# Schematics.net
KiCad netlist of a schematic drawn in Altium Designer
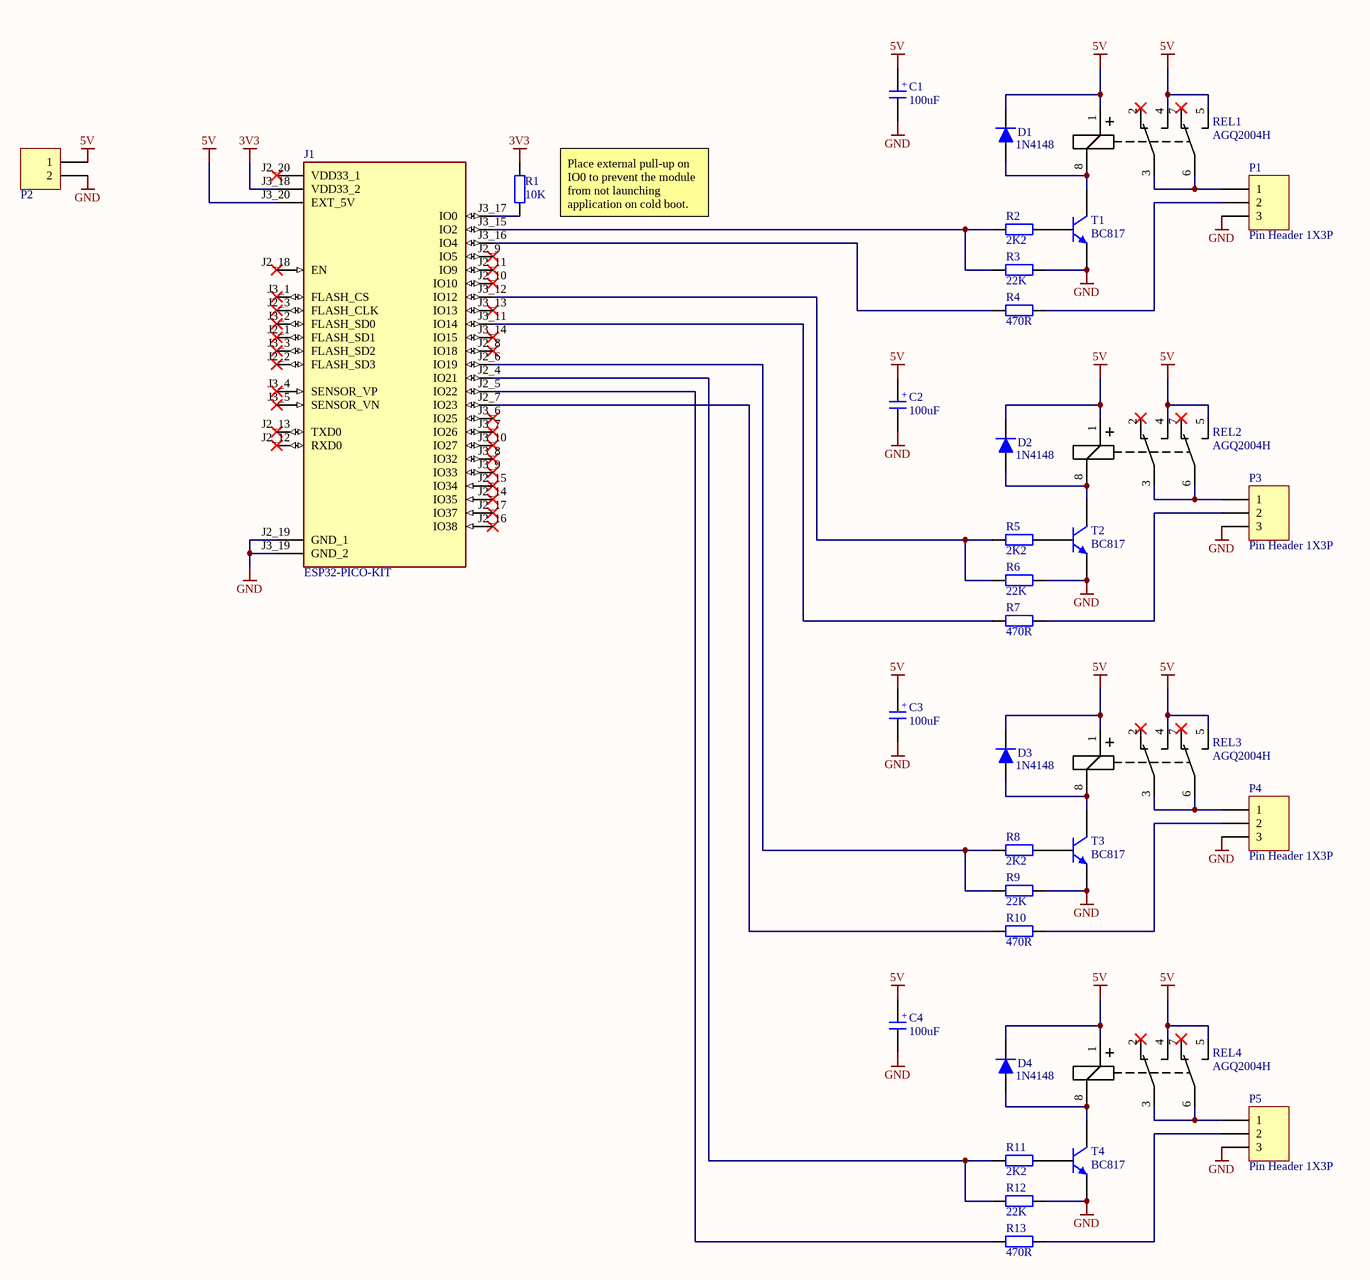
[diagram p0: Schematics.SchDoc]

(export (version "E")
  (design (tool "Eeschema 10.0.6"))
  (components
    (comp (ref "C1")
      (value "100uF")
      (footprint "EM-Alu-Elco_6,3X8_SMD")
      (description "Capacitor Elco")
      (libsource (lib "SchematicLibrary") (part "Capacitor Elco"))
    )
    (comp (ref "C2")
      (value "100uF")
      (footprint "EM-Alu-Elco_6,3X8_SMD")
      (description "Capacitor Elco")
      (libsource (lib "SchematicLibrary") (part "Capacitor Elco"))
    )
    (comp (ref "C3")
      (value "100uF")
      (footprint "EM-Alu-Elco_6,3X8_SMD")
      (description "Capacitor Elco")
      (libsource (lib "SchematicLibrary") (part "Capacitor Elco"))
    )
    (comp (ref "C4")
      (value "100uF")
      (footprint "EM-Alu-Elco_6,3X8_SMD")
      (description "Capacitor Elco")
      (libsource (lib "SchematicLibrary") (part "Capacitor Elco"))
    )
    (comp (ref "D1")
      (value "1N4148")
      (footprint "EM-SOD80C T1,5_SMD")
      (description "Diode")
      (libsource (lib "SchematicLibrary") (part "Diode"))
    )
    (comp (ref "D2")
      (value "1N4148")
      (footprint "EM-SOD80C T1,5_SMD")
      (description "Diode")
      (libsource (lib "SchematicLibrary") (part "Diode"))
    )
    (comp (ref "D3")
      (value "1N4148")
      (footprint "EM-SOD80C T1,5_SMD")
      (description "Diode")
      (libsource (lib "SchematicLibrary") (part "Diode"))
    )
    (comp (ref "D4")
      (value "1N4148")
      (footprint "EM-SOD80C T1,5_SMD")
      (description "Diode")
      (libsource (lib "SchematicLibrary") (part "Diode"))
    )
    (comp (ref "J1")
      (value "ESP32-PICO-KIT")
      (footprint "XCVR_ESP32-PICO-KIT")
      (fields (field (name "MF") "Espressif Systems"))
      (libsource (lib "SchematicLibrary") (part "ESP32-PICO-KIT"))
    )
    (comp (ref "P1")
      (value "Pin Header 1X3P")
      (footprint "JST XH B3B-XH-A")
      (description "Header 3-Pin")
      (fields (field (name "MANUFACTURER PART NO.") "61300311121"))
      (libsource (lib "SchematicLibrary") (part "Header 3"))
    )
    (comp (ref "P2")
      (value "Pin Header 1X2P")
      (footprint "JST XH B2B-XH-A")
      (description "Header 2-Pin")
      (fields (field (name "MANUFACTURER PART NO.") "61300211121"))
      (libsource (lib "SchematicLibrary") (part "Header 2"))
    )
    (comp (ref "P3")
      (value "Pin Header 1X3P")
      (footprint "JST XH B3B-XH-A")
      (description "Header 3-Pin")
      (fields (field (name "MANUFACTURER PART NO.") "61300311121"))
      (libsource (lib "SchematicLibrary") (part "Header 3"))
    )
    (comp (ref "P4")
      (value "Pin Header 1X3P")
      (footprint "JST XH B3B-XH-A")
      (description "Header 3-Pin")
      (fields (field (name "MANUFACTURER PART NO.") "61300311121"))
      (libsource (lib "SchematicLibrary") (part "Header 3"))
    )
    (comp (ref "P5")
      (value "Pin Header 1X3P")
      (footprint "JST XH B3B-XH-A")
      (description "Header 3-Pin")
      (fields (field (name "MANUFACTURER PART NO.") "61300311121"))
      (libsource (lib "SchematicLibrary") (part "Header 3"))
    )
    (comp (ref "R1")
      (value "10K")
      (footprint "EM-0603-R T0,45_SMD")
      (description "Resistor")
      (libsource (lib "") (part "Resistor_1"))
    )
    (comp (ref "R2")
      (value "2K2")
      (footprint "EM-0603-R T0,45_SMD")
      (description "Resistor")
      (libsource (lib "SchematicLibrary") (part "Resistor"))
    )
    (comp (ref "R3")
      (value "22K")
      (footprint "EM-0603-R T0,45_SMD")
      (description "Resistor")
      (libsource (lib "SchematicLibrary") (part "Resistor"))
    )
    (comp (ref "R4")
      (value "470R")
      (footprint "EM-0603-R T0,45_SMD")
      (description "Resistor")
      (libsource (lib "SchematicLibrary") (part "Resistor"))
    )
    (comp (ref "R5")
      (value "2K2")
      (footprint "EM-0603-R T0,45_SMD")
      (description "Resistor")
      (libsource (lib "SchematicLibrary") (part "Resistor"))
    )
    (comp (ref "R6")
      (value "22K")
      (footprint "EM-0603-R T0,45_SMD")
      (description "Resistor")
      (libsource (lib "SchematicLibrary") (part "Resistor"))
    )
    (comp (ref "R7")
      (value "470R")
      (footprint "EM-0603-R T0,45_SMD")
      (description "Resistor")
      (libsource (lib "SchematicLibrary") (part "Resistor"))
    )
    (comp (ref "R8")
      (value "2K2")
      (footprint "EM-0603-R T0,45_SMD")
      (description "Resistor")
      (libsource (lib "SchematicLibrary") (part "Resistor"))
    )
    (comp (ref "R9")
      (value "22K")
      (footprint "EM-0603-R T0,45_SMD")
      (description "Resistor")
      (libsource (lib "SchematicLibrary") (part "Resistor"))
    )
    (comp (ref "R10")
      (value "470R")
      (footprint "EM-0603-R T0,45_SMD")
      (description "Resistor")
      (libsource (lib "SchematicLibrary") (part "Resistor"))
    )
    (comp (ref "R11")
      (value "2K2")
      (footprint "EM-0603-R T0,45_SMD")
      (description "Resistor")
      (libsource (lib "SchematicLibrary") (part "Resistor"))
    )
    (comp (ref "R12")
      (value "22K")
      (footprint "EM-0603-R T0,45_SMD")
      (description "Resistor")
      (libsource (lib "SchematicLibrary") (part "Resistor"))
    )
    (comp (ref "R13")
      (value "470R")
      (footprint "EM-0603-R T0,45_SMD")
      (description "Resistor")
      (libsource (lib "SchematicLibrary") (part "Resistor"))
    )
    (comp (ref "REL1")
      (value "AGQ2004H")
      (footprint "THC Relay AGQ")
      (description "AGQ2004H -  Signal Relay, 4.5 VDC, DPDT, 2 A, Through Hole, Non Latching, AGQ Series")
      (fields (field (name "MANUFACTURER PART NO.") "TX2-4.5V") (field (name "TYPE") "AGQ2004H"))
      (libsource (lib "SchematicLibrary") (part "Relay AGQ2004H"))
    )
    (comp (ref "REL2")
      (value "AGQ2004H")
      (footprint "THC Relay AGQ")
      (description "AGQ2004H -  Signal Relay, 4.5 VDC, DPDT, 2 A, Through Hole, Non Latching, AGQ Series")
      (fields (field (name "MANUFACTURER PART NO.") "TX2-4.5V") (field (name "TYPE") "AGQ2004H"))
      (libsource (lib "SchematicLibrary") (part "Relay AGQ2004H"))
    )
    (comp (ref "REL3")
      (value "AGQ2004H")
      (footprint "THC Relay AGQ")
      (description "AGQ2004H -  Signal Relay, 4.5 VDC, DPDT, 2 A, Through Hole, Non Latching, AGQ Series")
      (fields (field (name "MANUFACTURER PART NO.") "TX2-4.5V") (field (name "TYPE") "AGQ2004H"))
      (libsource (lib "SchematicLibrary") (part "Relay AGQ2004H"))
    )
    (comp (ref "REL4")
      (value "AGQ2004H")
      (footprint "THC Relay AGQ")
      (description "AGQ2004H -  Signal Relay, 4.5 VDC, DPDT, 2 A, Through Hole, Non Latching, AGQ Series")
      (fields (field (name "MANUFACTURER PART NO.") "TX2-4.5V") (field (name "TYPE") "AGQ2004H"))
      (libsource (lib "SchematicLibrary") (part "Relay AGQ2004H"))
    )
    (comp (ref "T1")
      (value "BC817")
      (footprint "EM-SOT323_SMD")
      (description "BC817 -  Bipolar (BJT) Single Transistor, NPN, 45 V, 170 MHz, 300 mW, 500 mA, 100 hFE")
      (fields (field (name "MANUFACTURER PART NO.") "BC817W,115") (field (name "TYPE") "BC817"))
      (libsource (lib "SchematicLibrary") (part "Transistor BC817 (Small)"))
    )
    (comp (ref "T2")
      (value "BC817")
      (footprint "EM-SOT323_SMD")
      (description "BC817 -  Bipolar (BJT) Single Transistor, NPN, 45 V, 170 MHz, 300 mW, 500 mA, 100 hFE")
      (fields (field (name "MANUFACTURER PART NO.") "BC817W,115") (field (name "TYPE") "BC817"))
      (libsource (lib "SchematicLibrary") (part "Transistor BC817 (Small)"))
    )
    (comp (ref "T3")
      (value "BC817")
      (footprint "EM-SOT323_SMD")
      (description "BC817 -  Bipolar (BJT) Single Transistor, NPN, 45 V, 170 MHz, 300 mW, 500 mA, 100 hFE")
      (fields (field (name "MANUFACTURER PART NO.") "BC817W,115") (field (name "TYPE") "BC817"))
      (libsource (lib "SchematicLibrary") (part "Transistor BC817 (Small)"))
    )
    (comp (ref "T4")
      (value "BC817")
      (footprint "EM-SOT323_SMD")
      (description "BC817 -  Bipolar (BJT) Single Transistor, NPN, 45 V, 170 MHz, 300 mW, 500 mA, 100 hFE")
      (fields (field (name "MANUFACTURER PART NO.") "BC817W,115") (field (name "TYPE") "BC817"))
      (libsource (lib "SchematicLibrary") (part "Transistor BC817 (Small)"))
    )
  )
  (nets
    (net (code "1") (name "3V3") (class "Default")
      (node (ref "J1") (pin "J3_18") (pinfunction "VDD33_2_J3_18") (pintype "power_in"))
      (node (ref "R1") (pin "2") (pinfunction "2_2") (pintype "passive"))
    )
    (net (code "2") (name "5V") (class "Default")
      (node (ref "C1") (pin "1") (pinfunction "1_1") (pintype "passive"))
      (node (ref "C2") (pin "1") (pinfunction "1_1") (pintype "passive"))
      (node (ref "C3") (pin "1") (pinfunction "1_1") (pintype "passive"))
      (node (ref "C4") (pin "1") (pinfunction "1_1") (pintype "passive"))
      (node (ref "D1") (pin "1") (pinfunction "C_1") (pintype "passive"))
      (node (ref "D2") (pin "1") (pinfunction "C_1") (pintype "passive"))
      (node (ref "D3") (pin "1") (pinfunction "C_1") (pintype "passive"))
      (node (ref "D4") (pin "1") (pinfunction "C_1") (pintype "passive"))
      (node (ref "J1") (pin "J3_20") (pinfunction "EXT_5V_J3_20") (pintype "power_in"))
      (node (ref "P2") (pin "1") (pinfunction "1_1") (pintype "passive"))
      (node (ref "REL1") (pin "1") (pinfunction "1_1") (pintype "power_in"))
      (node (ref "REL1") (pin "4") (pinfunction "4_4") (pintype "power_in"))
      (node (ref "REL1") (pin "5") (pinfunction "5_5") (pintype "power_in"))
      (node (ref "REL2") (pin "1") (pinfunction "1_1") (pintype "power_in"))
      (node (ref "REL2") (pin "4") (pinfunction "4_4") (pintype "power_in"))
      (node (ref "REL2") (pin "5") (pinfunction "5_5") (pintype "power_in"))
      (node (ref "REL3") (pin "1") (pinfunction "1_1") (pintype "power_in"))
      (node (ref "REL3") (pin "4") (pinfunction "4_4") (pintype "power_in"))
      (node (ref "REL3") (pin "5") (pinfunction "5_5") (pintype "power_in"))
      (node (ref "REL4") (pin "1") (pinfunction "1_1") (pintype "power_in"))
      (node (ref "REL4") (pin "4") (pinfunction "4_4") (pintype "power_in"))
      (node (ref "REL4") (pin "5") (pinfunction "5_5") (pintype "power_in"))
    )
    (net (code "3") (name "GND") (class "Default")
      (node (ref "C1") (pin "2") (pinfunction "2_2") (pintype "passive"))
      (node (ref "C2") (pin "2") (pinfunction "2_2") (pintype "passive"))
      (node (ref "C3") (pin "2") (pinfunction "2_2") (pintype "passive"))
      (node (ref "C4") (pin "2") (pinfunction "2_2") (pintype "passive"))
      (node (ref "J1") (pin "J2_19") (pinfunction "GND_1_J2_19") (pintype "power_in"))
      (node (ref "J1") (pin "J3_19") (pinfunction "GND_2_J3_19") (pintype "power_in"))
      (node (ref "P1") (pin "3") (pinfunction "3_3") (pintype "passive"))
      (node (ref "P2") (pin "2") (pinfunction "2_2") (pintype "passive"))
      (node (ref "P3") (pin "3") (pinfunction "3_3") (pintype "passive"))
      (node (ref "P4") (pin "3") (pinfunction "3_3") (pintype "passive"))
      (node (ref "P5") (pin "3") (pinfunction "3_3") (pintype "passive"))
      (node (ref "R12") (pin "2") (pinfunction "2_2") (pintype "passive"))
      (node (ref "R3") (pin "2") (pinfunction "2_2") (pintype "passive"))
      (node (ref "R6") (pin "2") (pinfunction "2_2") (pintype "passive"))
      (node (ref "R9") (pin "2") (pinfunction "2_2") (pintype "passive"))
      (node (ref "T1") (pin "2") (pinfunction "E_2") (pintype "passive"))
      (node (ref "T2") (pin "2") (pinfunction "E_2") (pintype "passive"))
      (node (ref "T3") (pin "2") (pinfunction "E_2") (pintype "passive"))
      (node (ref "T4") (pin "2") (pinfunction "E_2") (pintype "passive"))
    )
    (net (code "4") (name "Net-(D1-A)") (class "Default")
      (node (ref "D1") (pin "2") (pinfunction "A_2") (pintype "passive"))
      (node (ref "REL1") (pin "8") (pinfunction "8_8") (pintype "power_in"))
      (node (ref "T1") (pin "3") (pinfunction "C_3") (pintype "passive"))
    )
    (net (code "5") (name "Net-(D2-A)") (class "Default")
      (node (ref "D2") (pin "2") (pinfunction "A_2") (pintype "passive"))
      (node (ref "REL2") (pin "8") (pinfunction "8_8") (pintype "power_in"))
      (node (ref "T2") (pin "3") (pinfunction "C_3") (pintype "passive"))
    )
    (net (code "6") (name "Net-(D3-A)") (class "Default")
      (node (ref "D3") (pin "2") (pinfunction "A_2") (pintype "passive"))
      (node (ref "REL3") (pin "8") (pinfunction "8_8") (pintype "power_in"))
      (node (ref "T3") (pin "3") (pinfunction "C_3") (pintype "passive"))
    )
    (net (code "7") (name "Net-(D4-A)") (class "Default")
      (node (ref "D4") (pin "2") (pinfunction "A_2") (pintype "passive"))
      (node (ref "REL4") (pin "8") (pinfunction "8_8") (pintype "power_in"))
      (node (ref "T4") (pin "3") (pinfunction "C_3") (pintype "passive"))
    )
    (net (code "8") (name "Net-(J1-IO0)") (class "Default")
      (node (ref "J1") (pin "J3_17") (pinfunction "IO0_J3_17") (pintype "bidirectional"))
      (node (ref "R1") (pin "1") (pinfunction "1_1") (pintype "passive"))
    )
    (net (code "9") (name "Net-(J1-IO2)") (class "Default")
      (node (ref "J1") (pin "J3_15") (pinfunction "IO2_J3_15") (pintype "bidirectional"))
      (node (ref "R2") (pin "1") (pinfunction "1_1") (pintype "passive"))
      (node (ref "R3") (pin "1") (pinfunction "1_1") (pintype "passive"))
    )
    (net (code "10") (name "Net-(J1-IO4)") (class "Default")
      (node (ref "J1") (pin "J3_16") (pinfunction "IO4_J3_16") (pintype "bidirectional"))
      (node (ref "R4") (pin "1") (pinfunction "1_1") (pintype "passive"))
    )
    (net (code "11") (name "Net-(J1-IO12)") (class "Default")
      (node (ref "J1") (pin "J3_12") (pinfunction "IO12_J3_12") (pintype "bidirectional"))
      (node (ref "R5") (pin "1") (pinfunction "1_1") (pintype "passive"))
      (node (ref "R6") (pin "1") (pinfunction "1_1") (pintype "passive"))
    )
    (net (code "12") (name "Net-(J1-IO14)") (class "Default")
      (node (ref "J1") (pin "J3_11") (pinfunction "IO14_J3_11") (pintype "bidirectional"))
      (node (ref "R7") (pin "1") (pinfunction "1_1") (pintype "passive"))
    )
    (net (code "13") (name "Net-(J1-IO19)") (class "Default")
      (node (ref "J1") (pin "J2_6") (pinfunction "IO19_J2_6") (pintype "bidirectional"))
      (node (ref "R8") (pin "1") (pinfunction "1_1") (pintype "passive"))
      (node (ref "R9") (pin "1") (pinfunction "1_1") (pintype "passive"))
    )
    (net (code "14") (name "Net-(J1-IO21)") (class "Default")
      (node (ref "J1") (pin "J2_4") (pinfunction "IO21_J2_4") (pintype "bidirectional"))
      (node (ref "R11") (pin "1") (pinfunction "1_1") (pintype "passive"))
      (node (ref "R12") (pin "1") (pinfunction "1_1") (pintype "passive"))
    )
    (net (code "15") (name "Net-(J1-IO22)") (class "Default")
      (node (ref "J1") (pin "J2_5") (pinfunction "IO22_J2_5") (pintype "bidirectional"))
      (node (ref "R13") (pin "1") (pinfunction "1_1") (pintype "passive"))
    )
    (net (code "16") (name "Net-(J1-IO23)") (class "Default")
      (node (ref "J1") (pin "J2_7") (pinfunction "IO23_J2_7") (pintype "bidirectional"))
      (node (ref "R10") (pin "1") (pinfunction "1_1") (pintype "passive"))
    )
    (net (code "17") (name "Net-(P1-Pad1)") (class "Default")
      (node (ref "P1") (pin "1") (pinfunction "1_1") (pintype "passive"))
      (node (ref "REL1") (pin "3") (pinfunction "3_3") (pintype "power_in"))
      (node (ref "REL1") (pin "6") (pinfunction "6_6") (pintype "power_in"))
    )
    (net (code "18") (name "Net-(P1-Pad2)") (class "Default")
      (node (ref "P1") (pin "2") (pinfunction "2_2") (pintype "passive"))
      (node (ref "R4") (pin "2") (pinfunction "2_2") (pintype "passive"))
    )
    (net (code "19") (name "Net-(P3-Pad1)") (class "Default")
      (node (ref "P3") (pin "1") (pinfunction "1_1") (pintype "passive"))
      (node (ref "REL2") (pin "3") (pinfunction "3_3") (pintype "power_in"))
      (node (ref "REL2") (pin "6") (pinfunction "6_6") (pintype "power_in"))
    )
    (net (code "20") (name "Net-(P3-Pad2)") (class "Default")
      (node (ref "P3") (pin "2") (pinfunction "2_2") (pintype "passive"))
      (node (ref "R7") (pin "2") (pinfunction "2_2") (pintype "passive"))
    )
    (net (code "21") (name "Net-(P4-Pad1)") (class "Default")
      (node (ref "P4") (pin "1") (pinfunction "1_1") (pintype "passive"))
      (node (ref "REL3") (pin "3") (pinfunction "3_3") (pintype "power_in"))
      (node (ref "REL3") (pin "6") (pinfunction "6_6") (pintype "power_in"))
    )
    (net (code "22") (name "Net-(P4-Pad2)") (class "Default")
      (node (ref "P4") (pin "2") (pinfunction "2_2") (pintype "passive"))
      (node (ref "R10") (pin "2") (pinfunction "2_2") (pintype "passive"))
    )
    (net (code "23") (name "Net-(P5-Pad1)") (class "Default")
      (node (ref "P5") (pin "1") (pinfunction "1_1") (pintype "passive"))
      (node (ref "REL4") (pin "3") (pinfunction "3_3") (pintype "power_in"))
      (node (ref "REL4") (pin "6") (pinfunction "6_6") (pintype "power_in"))
    )
    (net (code "24") (name "Net-(P5-Pad2)") (class "Default")
      (node (ref "P5") (pin "2") (pinfunction "2_2") (pintype "passive"))
      (node (ref "R13") (pin "2") (pinfunction "2_2") (pintype "passive"))
    )
    (net (code "25") (name "Net-(T1-B)") (class "Default")
      (node (ref "R2") (pin "2") (pinfunction "2_2") (pintype "passive"))
      (node (ref "T1") (pin "1") (pinfunction "B_1") (pintype "passive"))
    )
    (net (code "26") (name "Net-(T2-B)") (class "Default")
      (node (ref "R5") (pin "2") (pinfunction "2_2") (pintype "passive"))
      (node (ref "T2") (pin "1") (pinfunction "B_1") (pintype "passive"))
    )
    (net (code "27") (name "Net-(T3-B)") (class "Default")
      (node (ref "R8") (pin "2") (pinfunction "2_2") (pintype "passive"))
      (node (ref "T3") (pin "1") (pinfunction "B_1") (pintype "passive"))
    )
    (net (code "28") (name "Net-(T4-B)") (class "Default")
      (node (ref "R11") (pin "2") (pinfunction "2_2") (pintype "passive"))
      (node (ref "T4") (pin "1") (pinfunction "B_1") (pintype "passive"))
    )
    (net (code "29") (name "unconnected-(J1-EN-PadJ2_18)") (class "Default")
      (node (ref "J1") (pin "J2_18") (pinfunction "EN_J2_18") (pintype "input+no_connect"))
    )
    (net (code "30") (name "unconnected-(J1-FLASH_CLK-PadJ2_3)") (class "Default")
      (node (ref "J1") (pin "J2_3") (pinfunction "FLASH_CLK_J2_3") (pintype "bidirectional+no_connect"))
    )
    (net (code "31") (name "unconnected-(J1-FLASH_CS-PadJ3_1)") (class "Default")
      (node (ref "J1") (pin "J3_1") (pinfunction "FLASH_CS_J3_1") (pintype "bidirectional+no_connect"))
    )
    (net (code "32") (name "unconnected-(J1-FLASH_SD0-PadJ3_2)") (class "Default")
      (node (ref "J1") (pin "J3_2") (pinfunction "FLASH_SD0_J3_2") (pintype "bidirectional+no_connect"))
    )
    (net (code "33") (name "unconnected-(J1-FLASH_SD1-PadJ2_1)") (class "Default")
      (node (ref "J1") (pin "J2_1") (pinfunction "FLASH_SD1_J2_1") (pintype "bidirectional+no_connect"))
    )
    (net (code "34") (name "unconnected-(J1-FLASH_SD2-PadJ3_3)") (class "Default")
      (node (ref "J1") (pin "J3_3") (pinfunction "FLASH_SD2_J3_3") (pintype "bidirectional+no_connect"))
    )
    (net (code "35") (name "unconnected-(J1-FLASH_SD3-PadJ2_2)") (class "Default")
      (node (ref "J1") (pin "J2_2") (pinfunction "FLASH_SD3_J2_2") (pintype "bidirectional+no_connect"))
    )
    (net (code "36") (name "unconnected-(J1-IO5-PadJ2_9)") (class "Default")
      (node (ref "J1") (pin "J2_9") (pinfunction "IO5_J2_9") (pintype "bidirectional+no_connect"))
    )
    (net (code "37") (name "unconnected-(J1-IO9-PadJ2_11)") (class "Default")
      (node (ref "J1") (pin "J2_11") (pinfunction "IO9_J2_11") (pintype "bidirectional+no_connect"))
    )
    (net (code "38") (name "unconnected-(J1-IO10-PadJ2_10)") (class "Default")
      (node (ref "J1") (pin "J2_10") (pinfunction "IO10_J2_10") (pintype "bidirectional+no_connect"))
    )
    (net (code "39") (name "unconnected-(J1-IO13-PadJ3_13)") (class "Default")
      (node (ref "J1") (pin "J3_13") (pinfunction "IO13_J3_13") (pintype "bidirectional+no_connect"))
    )
    (net (code "40") (name "unconnected-(J1-IO15-PadJ3_14)") (class "Default")
      (node (ref "J1") (pin "J3_14") (pinfunction "IO15_J3_14") (pintype "bidirectional+no_connect"))
    )
    (net (code "41") (name "unconnected-(J1-IO18-PadJ2_8)") (class "Default")
      (node (ref "J1") (pin "J2_8") (pinfunction "IO18_J2_8") (pintype "bidirectional+no_connect"))
    )
    (net (code "42") (name "unconnected-(J1-IO25-PadJ3_6)") (class "Default")
      (node (ref "J1") (pin "J3_6") (pinfunction "IO25_J3_6") (pintype "bidirectional+no_connect"))
    )
    (net (code "43") (name "unconnected-(J1-IO26-PadJ3_7)") (class "Default")
      (node (ref "J1") (pin "J3_7") (pinfunction "IO26_J3_7") (pintype "bidirectional+no_connect"))
    )
    (net (code "44") (name "unconnected-(J1-IO27-PadJ3_10)") (class "Default")
      (node (ref "J1") (pin "J3_10") (pinfunction "IO27_J3_10") (pintype "bidirectional+no_connect"))
    )
    (net (code "45") (name "unconnected-(J1-IO32-PadJ3_8)") (class "Default")
      (node (ref "J1") (pin "J3_8") (pinfunction "IO32_J3_8") (pintype "bidirectional+no_connect"))
    )
    (net (code "46") (name "unconnected-(J1-IO33-PadJ3_9)") (class "Default")
      (node (ref "J1") (pin "J3_9") (pinfunction "IO33_J3_9") (pintype "bidirectional+no_connect"))
    )
    (net (code "47") (name "unconnected-(J1-IO34-PadJ2_15)") (class "Default")
      (node (ref "J1") (pin "J2_15") (pinfunction "IO34_J2_15") (pintype "input+no_connect"))
    )
    (net (code "48") (name "unconnected-(J1-IO35-PadJ2_14)") (class "Default")
      (node (ref "J1") (pin "J2_14") (pinfunction "IO35_J2_14") (pintype "input+no_connect"))
    )
    (net (code "49") (name "unconnected-(J1-IO37-PadJ2_17)") (class "Default")
      (node (ref "J1") (pin "J2_17") (pinfunction "IO37_J2_17") (pintype "input+no_connect"))
    )
    (net (code "50") (name "unconnected-(J1-IO38-PadJ2_16)") (class "Default")
      (node (ref "J1") (pin "J2_16") (pinfunction "IO38_J2_16") (pintype "input+no_connect"))
    )
    (net (code "51") (name "unconnected-(J1-RXD0-PadJ2_12)") (class "Default")
      (node (ref "J1") (pin "J2_12") (pinfunction "RXD0_J2_12") (pintype "bidirectional+no_connect"))
    )
    (net (code "52") (name "unconnected-(J1-SENSOR_VN-PadJ3_5)") (class "Default")
      (node (ref "J1") (pin "J3_5") (pinfunction "SENSOR_VN_J3_5") (pintype "input+no_connect"))
    )
    (net (code "53") (name "unconnected-(J1-SENSOR_VP-PadJ3_4)") (class "Default")
      (node (ref "J1") (pin "J3_4") (pinfunction "SENSOR_VP_J3_4") (pintype "input+no_connect"))
    )
    (net (code "54") (name "unconnected-(J1-TXD0-PadJ2_13)") (class "Default")
      (node (ref "J1") (pin "J2_13") (pinfunction "TXD0_J2_13") (pintype "bidirectional+no_connect"))
    )
    (net (code "55") (name "unconnected-(J1-VDD33_1-PadJ2_20)") (class "Default")
      (node (ref "J1") (pin "J2_20") (pinfunction "VDD33_1_J2_20") (pintype "power_in+no_connect"))
    )
    (net (code "56") (name "unconnected-(REL1-Pad2)") (class "Default")
      (node (ref "REL1") (pin "2") (pinfunction "2_2") (pintype "power_in+no_connect"))
    )
    (net (code "57") (name "unconnected-(REL1-Pad7)") (class "Default")
      (node (ref "REL1") (pin "7") (pinfunction "7_7") (pintype "power_in+no_connect"))
    )
    (net (code "58") (name "unconnected-(REL2-Pad2)") (class "Default")
      (node (ref "REL2") (pin "2") (pinfunction "2_2") (pintype "power_in+no_connect"))
    )
    (net (code "59") (name "unconnected-(REL2-Pad7)") (class "Default")
      (node (ref "REL2") (pin "7") (pinfunction "7_7") (pintype "power_in+no_connect"))
    )
    (net (code "60") (name "unconnected-(REL3-Pad2)") (class "Default")
      (node (ref "REL3") (pin "2") (pinfunction "2_2") (pintype "power_in+no_connect"))
    )
    (net (code "61") (name "unconnected-(REL3-Pad7)") (class "Default")
      (node (ref "REL3") (pin "7") (pinfunction "7_7") (pintype "power_in+no_connect"))
    )
    (net (code "62") (name "unconnected-(REL4-Pad2)") (class "Default")
      (node (ref "REL4") (pin "2") (pinfunction "2_2") (pintype "power_in+no_connect"))
    )
    (net (code "63") (name "unconnected-(REL4-Pad7)") (class "Default")
      (node (ref "REL4") (pin "7") (pinfunction "7_7") (pintype "power_in+no_connect"))
    )
  )
)
